# 12A-02.net
KiCad netlist of a schematic drawn in EAGLE
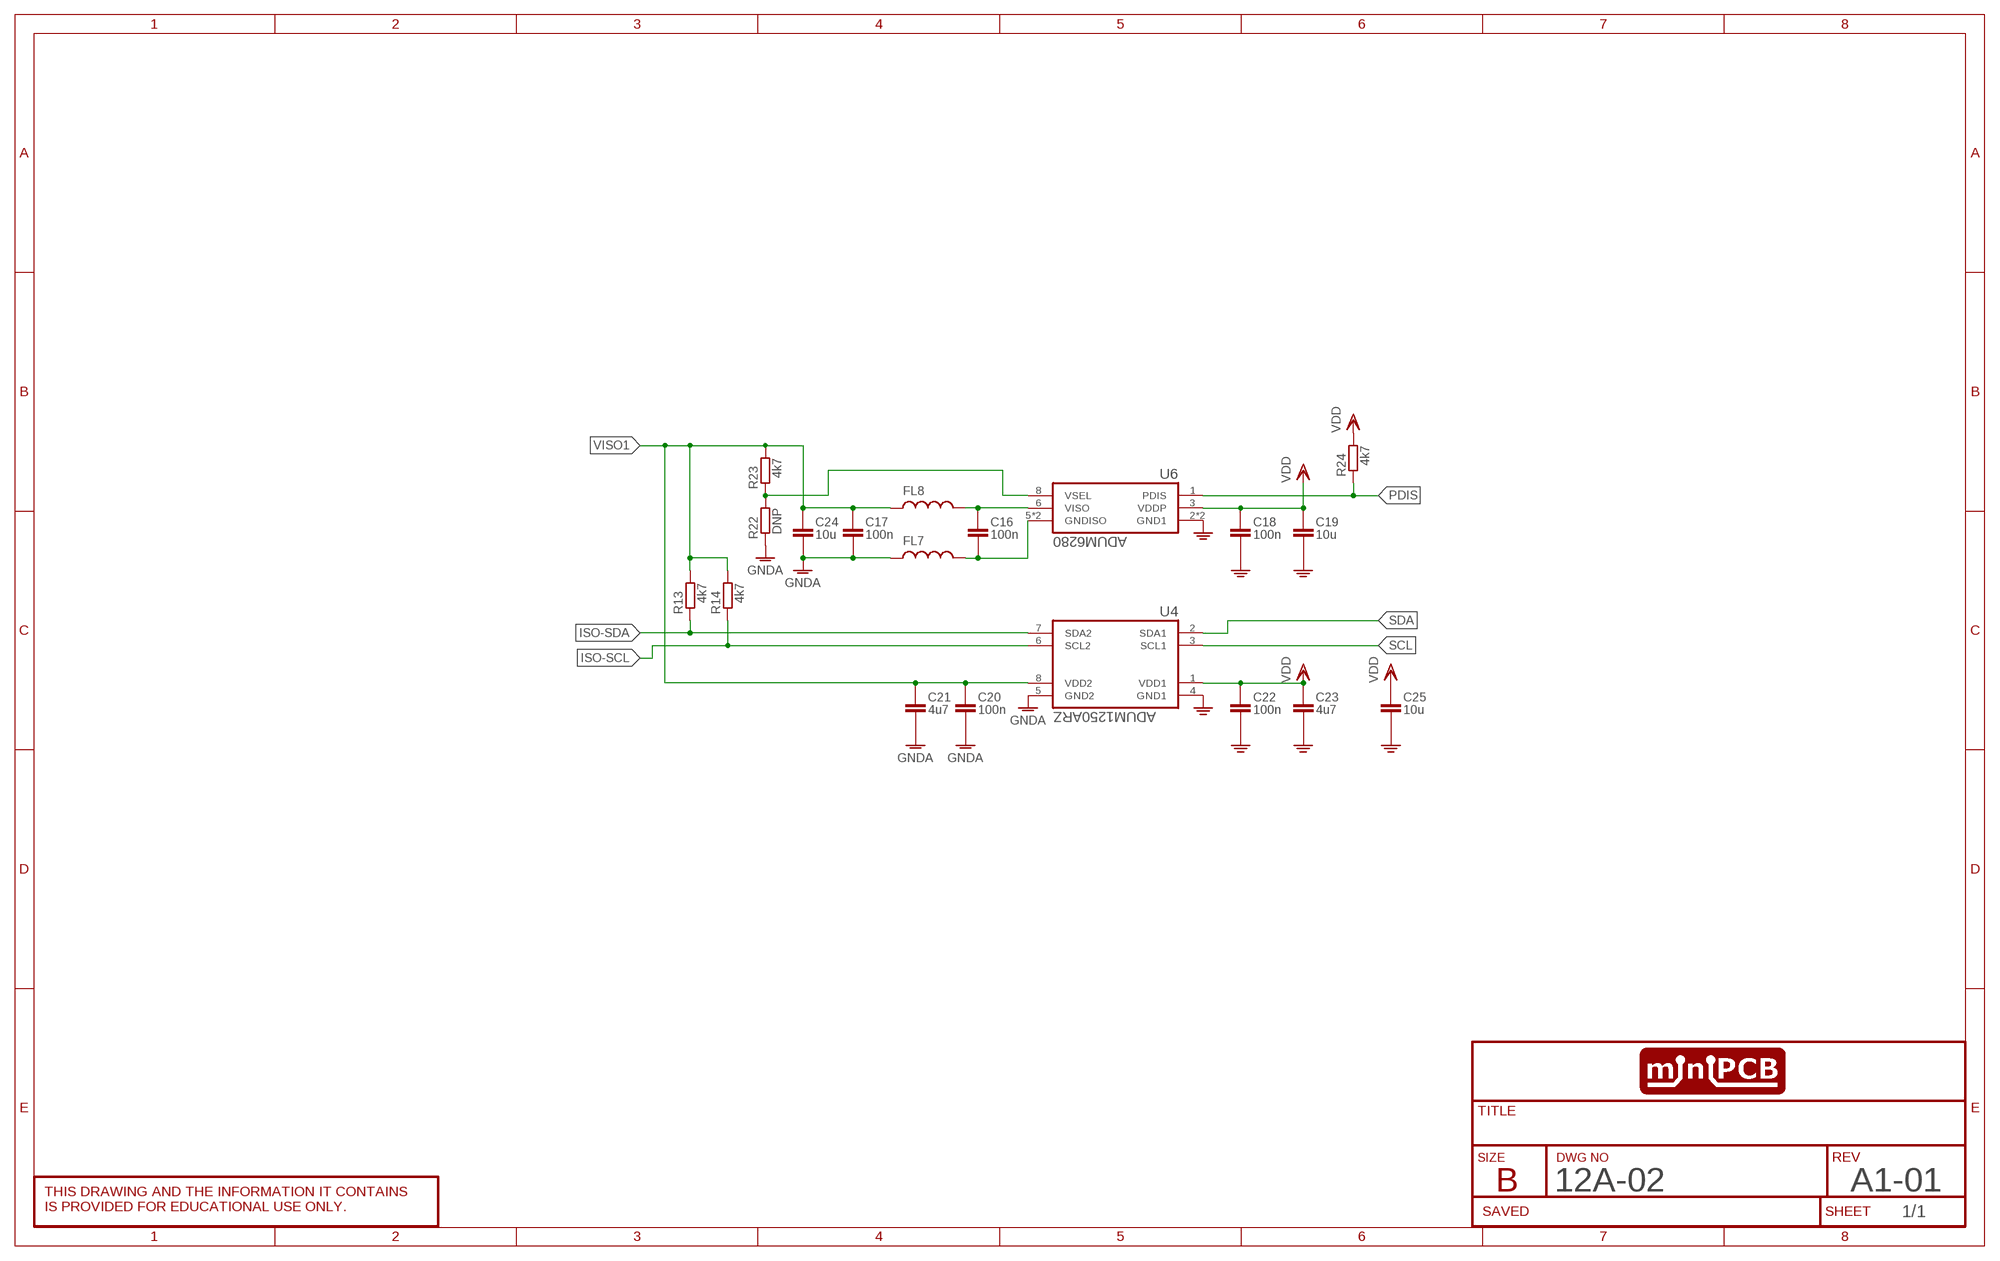
[diagram p0: schematic, sheet 1]

(export (version "E")
  (design (tool "Eeschema 10.0.6"))
  (components
    (comp (ref "C16")
      (value "100n")
      (footprint "eagle-import:C0402")
      (libsource (lib "eagle-import") (part "CAPACITOR0402"))
    )
    (comp (ref "C17")
      (value "100n")
      (footprint "eagle-import:C0402")
      (libsource (lib "eagle-import") (part "CAPACITOR0402"))
    )
    (comp (ref "C18")
      (value "100n")
      (footprint "eagle-import:C0402")
      (libsource (lib "eagle-import") (part "CAPACITOR0402"))
    )
    (comp (ref "C19")
      (value "10u")
      (footprint "eagle-import:C0805")
      (libsource (lib "eagle-import") (part "CAPACITORSMD"))
    )
    (comp (ref "C20")
      (value "100n")
      (footprint "eagle-import:C0402")
      (libsource (lib "eagle-import") (part "CAPACITOR0402"))
    )
    (comp (ref "C21")
      (value "4u7")
      (footprint "eagle-import:C0402")
      (libsource (lib "eagle-import") (part "CAPACITOR0402"))
    )
    (comp (ref "C22")
      (value "100n")
      (footprint "eagle-import:C0402")
      (libsource (lib "eagle-import") (part "CAPACITOR0402"))
    )
    (comp (ref "C23")
      (value "4u7")
      (footprint "eagle-import:C0402")
      (libsource (lib "eagle-import") (part "CAPACITOR0402"))
    )
    (comp (ref "C24")
      (value "10u")
      (footprint "eagle-import:C0805")
      (libsource (lib "eagle-import") (part "CAPACITORSMD"))
    )
    (comp (ref "C25")
      (value "10u")
      (footprint "eagle-import:C0805")
      (libsource (lib "eagle-import") (part "CAPACITORSMD"))
    )
    (comp (ref "FL7")
      (value "BLM03HG601SZ1D")
      (footprint "eagle-import:R0402")
      (libsource (lib "eagle-import") (part "BLM03HG601SZ1D"))
    )
    (comp (ref "FL8")
      (value "BLM03HG601SZ1D")
      (footprint "eagle-import:R0402")
      (libsource (lib "eagle-import") (part "BLM03HG601SZ1D"))
    )
    (comp (ref "R13")
      (value "4k7")
      (footprint "eagle-import:R0402")
      (libsource (lib "eagle-import") (part "RESISTOR0402"))
    )
    (comp (ref "R14")
      (value "4k7")
      (footprint "eagle-import:R0402")
      (libsource (lib "eagle-import") (part "RESISTOR0402"))
    )
    (comp (ref "R22")
      (value "DNP")
      (footprint "eagle-import:R0402")
      (libsource (lib "eagle-import") (part "RESISTOR0402"))
    )
    (comp (ref "R23")
      (value "4k7")
      (footprint "eagle-import:R0402")
      (libsource (lib "eagle-import") (part "RESISTOR0402"))
    )
    (comp (ref "R24")
      (value "4k7")
      (footprint "eagle-import:R0402")
      (libsource (lib "eagle-import") (part "RESISTOR0402"))
    )
    (comp (ref "U4")
      (value "ADUM1250ARZ")
      (footprint "eagle-import:SOIC127P600X175-8N")
      (fields (field (name "MF") "Analog Devices"))
      (libsource (lib "eagle-import") (part "ADUM1250ARZ"))
    )
    (comp (ref "U6")
      (value "ADUM6280")
      (footprint "eagle-import:SOIC127P600X175-8N")
      (libsource (lib "eagle-import") (part "ADUM6280"))
    )
  )
  (nets
    (net (code "1") (name "GND") (class "Default")
      (node (ref "C18") (pin "2") (pinfunction "-_2") (pintype "passive"))
      (node (ref "C19") (pin "2ASDF") (pinfunction "-_2ASDF") (pintype "passive"))
      (node (ref "C22") (pin "2") (pinfunction "-_2") (pintype "passive"))
      (node (ref "C23") (pin "2") (pinfunction "-_2") (pintype "passive"))
      (node (ref "C25") (pin "2ASDF") (pinfunction "-_2ASDF") (pintype "passive"))
      (node (ref "U4") (pin "4") (pinfunction "GND1_4") (pintype "passive"))
      (node (ref "U6") (pin "2") (pinfunction "GND1_2") (pintype "passive"))
      (node (ref "U6") (pin "4") (pinfunction "GND1_4") (pintype "passive"))
    )
    (net (code "2") (name "GNDA") (class "Default")
      (node (ref "C17") (pin "2") (pinfunction "-_2") (pintype "passive"))
      (node (ref "C20") (pin "2") (pinfunction "-_2") (pintype "passive"))
      (node (ref "C21") (pin "2") (pinfunction "-_2") (pintype "passive"))
      (node (ref "C24") (pin "2ASDF") (pinfunction "-_2ASDF") (pintype "passive"))
      (node (ref "FL7") (pin "1") (pinfunction "1_1") (pintype "passive"))
      (node (ref "R22") (pin "1") (pinfunction "1_1") (pintype "passive"))
      (node (ref "U4") (pin "5") (pinfunction "GND2_5") (pintype "passive"))
    )
    (net (code "3") (name "ISO-SCL") (class "Default")
      (node (ref "R14") (pin "1") (pinfunction "1_1") (pintype "passive"))
      (node (ref "U4") (pin "6") (pinfunction "SCL2_6") (pintype "input"))
    )
    (net (code "4") (name "ISO-SDA") (class "Default")
      (node (ref "R13") (pin "1") (pinfunction "1_1") (pintype "passive"))
      (node (ref "U4") (pin "7") (pinfunction "SDA2_7") (pintype "bidirectional"))
    )
    (net (code "5") (name "Net-(C16-+)") (class "Default")
      (node (ref "C16") (pin "1") (pinfunction "+_1") (pintype "passive"))
      (node (ref "FL8") (pin "2") (pinfunction "2_2") (pintype "passive"))
      (node (ref "U6") (pin "6") (pinfunction "VISO_6") (pintype "power_in"))
    )
    (net (code "6") (name "Net-(C16--)") (class "Default")
      (node (ref "C16") (pin "2") (pinfunction "-_2") (pintype "passive"))
      (node (ref "FL7") (pin "2") (pinfunction "2_2") (pintype "passive"))
      (node (ref "U6") (pin "5") (pinfunction "GNDISO_5") (pintype "passive"))
      (node (ref "U6") (pin "7") (pinfunction "GNDISO_7") (pintype "passive"))
    )
    (net (code "7") (name "Net-(U6-VSEL)") (class "Default")
      (node (ref "R22") (pin "2") (pinfunction "2_2") (pintype "passive"))
      (node (ref "R23") (pin "1") (pinfunction "1_1") (pintype "passive"))
      (node (ref "U6") (pin "8") (pinfunction "VSEL_8") (pintype "power_in"))
    )
    (net (code "8") (name "PDIS") (class "Default")
      (node (ref "R24") (pin "1") (pinfunction "1_1") (pintype "passive"))
      (node (ref "U6") (pin "1") (pinfunction "PDIS_1") (pintype "power_in"))
    )
    (net (code "9") (name "SCL") (class "Default")
      (node (ref "U4") (pin "3") (pinfunction "SCL1_3") (pintype "input"))
    )
    (net (code "10") (name "SDA") (class "Default")
      (node (ref "U4") (pin "2") (pinfunction "SDA1_2") (pintype "bidirectional"))
    )
    (net (code "11") (name "VDD") (class "Default")
      (node (ref "C18") (pin "1") (pinfunction "+_1") (pintype "passive"))
      (node (ref "C19") (pin "1ASD") (pinfunction "+_1ASD") (pintype "passive"))
      (node (ref "C22") (pin "1") (pinfunction "+_1") (pintype "passive"))
      (node (ref "C23") (pin "1") (pinfunction "+_1") (pintype "passive"))
      (node (ref "C25") (pin "1ASD") (pinfunction "+_1ASD") (pintype "passive"))
      (node (ref "R24") (pin "2") (pinfunction "2_2") (pintype "passive"))
      (node (ref "U4") (pin "1") (pinfunction "VDD1_1") (pintype "power_in"))
      (node (ref "U6") (pin "3") (pinfunction "VDDP_3") (pintype "bidirectional"))
    )
    (net (code "12") (name "VISO1") (class "Default")
      (node (ref "C17") (pin "1") (pinfunction "+_1") (pintype "passive"))
      (node (ref "C20") (pin "1") (pinfunction "+_1") (pintype "passive"))
      (node (ref "C21") (pin "1") (pinfunction "+_1") (pintype "passive"))
      (node (ref "C24") (pin "1ASD") (pinfunction "+_1ASD") (pintype "passive"))
      (node (ref "FL8") (pin "1") (pinfunction "1_1") (pintype "passive"))
      (node (ref "R13") (pin "2") (pinfunction "2_2") (pintype "passive"))
      (node (ref "R14") (pin "2") (pinfunction "2_2") (pintype "passive"))
      (node (ref "R23") (pin "2") (pinfunction "2_2") (pintype "passive"))
      (node (ref "U4") (pin "8") (pinfunction "VDD2_8") (pintype "power_in"))
    )
  )
)
